# HDMI_CONN_POWER_IN.net
KiCad netlist of a schematic drawn in Altium Designer
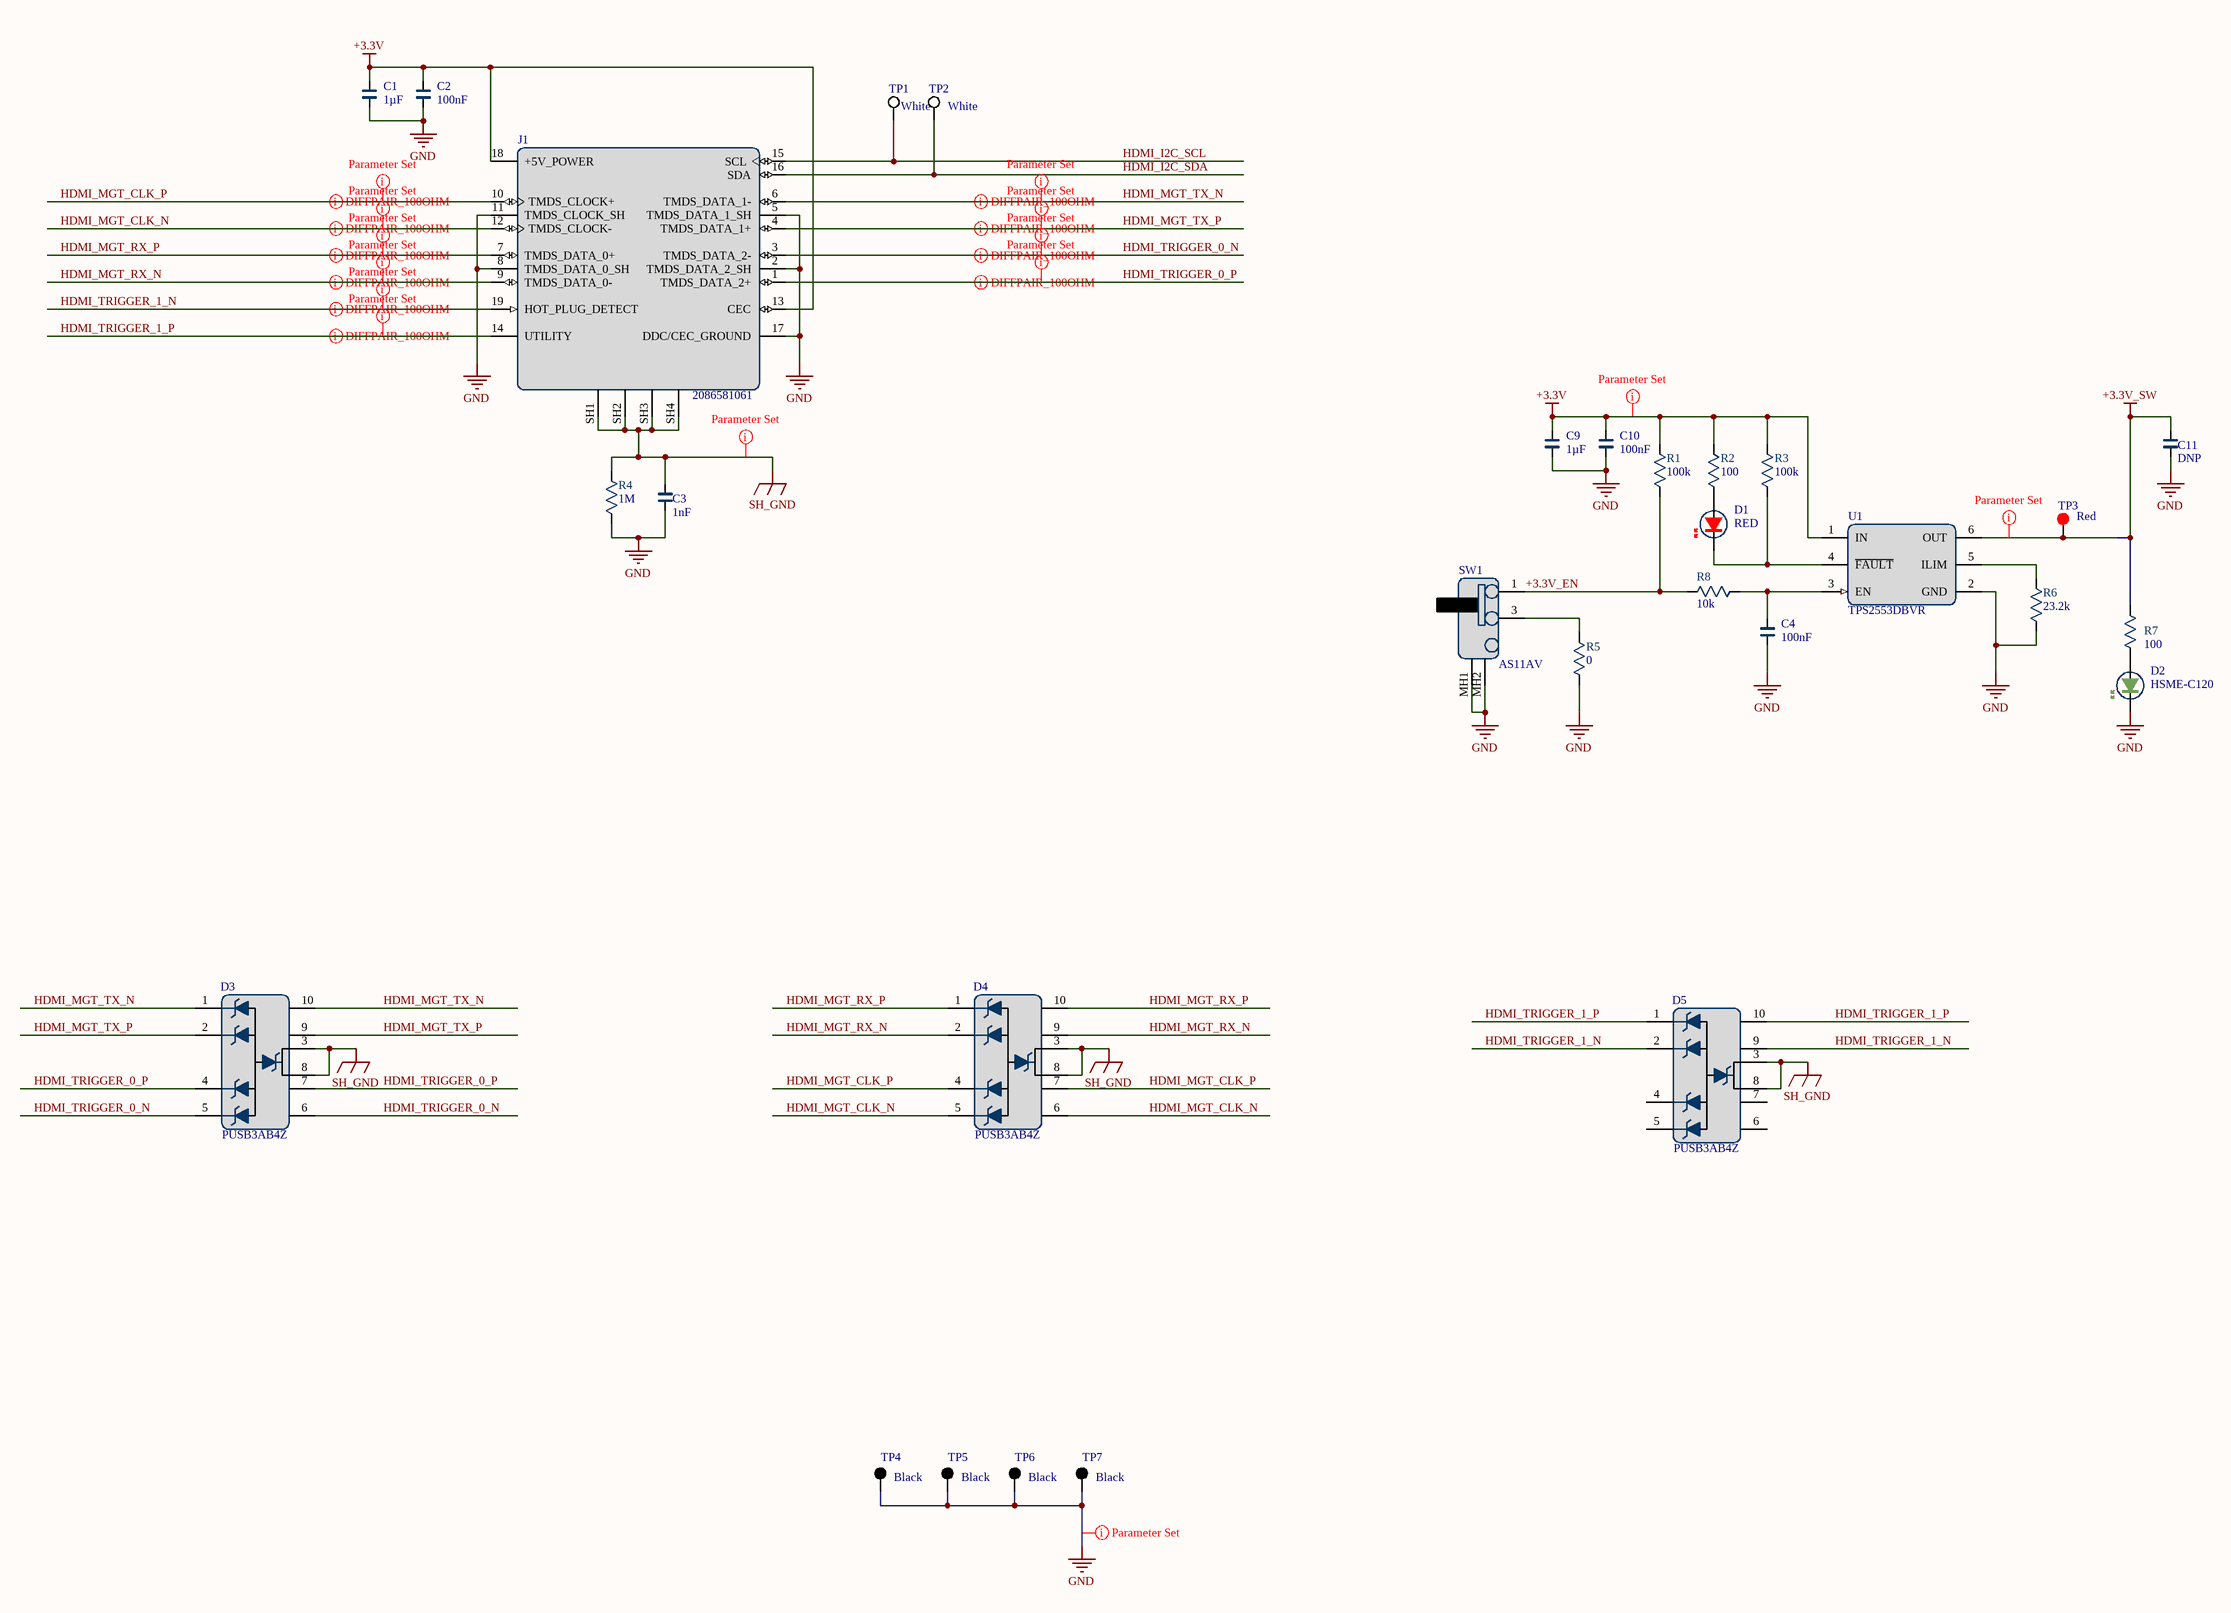
[diagram p0: HDMI_CONN_POWER_IN.SchDoc]

(export (version "E")
  (design (tool "Eeschema 10.0.6"))
  (components
    (comp (ref "C1")
      (value "1µF")
      (footprint "CAPC160X80X95L35")
      (description "CAP CER 1uF 10V 10% 0603")
      (fields (field (name "VOLTAGE") "10V") (field (name "TOLERANCE") "10%"))
      (libsource (lib "Atom Computing") (part "CAP"))
    )
    (comp (ref "C2")
      (value "100nF")
      (footprint "CAPC160X80X95L35")
      (description "CAP CER 0.1UF 25V X7R 0603")
      (fields (field (name "VOLTAGE") "25V") (field (name "TOLERANCE") "10%"))
      (libsource (lib "Atom Computing") (part "CAP"))
    )
    (comp (ref "C3")
      (value "1nF")
      (footprint "CAPC160X80X95L35")
      (description "CAP CER 1000PF 50V C0G/NPO 0603")
      (fields (field (name "TOLERANCE") "5%") (field (name "VOLTAGE") "50V"))
      (libsource (lib "Atom Computing") (part "CAP"))
    )
    (comp (ref "C4")
      (value "100nF")
      (footprint "CAPC160X80X95L35")
      (description "CAP CER 0.1UF 25V X7R 0603")
      (fields (field (name "TOLERANCE") "10%") (field (name "MFG") "Kemet"))
      (libsource (lib "Atom Computing") (part "CAP"))
    )
    (comp (ref "C9")
      (value "1µF")
      (footprint "CAPC160X80X95L35")
      (description "CAP CER 1uF 10V 10% 0603")
      (fields (field (name "VOLTAGE") "10V") (field (name "TOLERANCE") "10%"))
      (libsource (lib "Atom Computing") (part "CAP"))
    )
    (comp (ref "C10")
      (value "100nF")
      (footprint "CAPC160X80X95L35")
      (description "CAP CER 0.1UF 25V X7R 0603")
      (fields (field (name "VOLTAGE") "25V") (field (name "TOLERANCE") "10%"))
      (libsource (lib "Atom Computing") (part "CAP"))
    )
    (comp (ref "C11")
      (value "DNP")
      (footprint "CAPC200X125X145L50")
      (description "DNP, CAP 0805")
      (libsource (lib "Atom Computing") (part "CAP"))
    )
    (comp (ref "D1")
      (value "RED")
      (footprint "LEDSC80X160X55L40X70_C1A2")
      (description "LED RED CLEAR CHIP SMD 629nm, 1.9V, 0603")
      (fields (field (name "MFG") "Lite-On Inc.") (field (name "VOLTAGE") "2V"))
      (libsource (lib "Atom Computing") (part "LED_RED"))
    )
    (comp (ref "D2")
      (value "HSME-C120")
      (footprint "BROADCOM_HSMX-C120")
      (description "LED GREEN CLEAR CHIP SMD R/A")
      (fields (field (name "MFG") "AVAGO TECHNOLOGIES"))
      (libsource (lib "Atom Computing") (part "LED_GREEN"))
    )
    (comp (ref "D3")
      (value "PUSB3AB4Z")
      (footprint "NEXPERIA_PUSB3AB4Z")
      (description "TVS DIODE BIDIRECTIONAL 3.3VWM 5VC DFN2510A-10")
      (fields (field (name "MFG") "Nexperia USA Inc."))
      (libsource (lib "Atom Computing") (part "PUSB3AB4Z"))
    )
    (comp (ref "D4")
      (value "PUSB3AB4Z")
      (footprint "NEXPERIA_PUSB3AB4Z")
      (description "TVS DIODE BIDIRECTIONAL 3.3VWM 5VC DFN2510A-10")
      (fields (field (name "MFG") "Nexperia USA Inc."))
      (libsource (lib "Atom Computing") (part "PUSB3AB4Z"))
    )
    (comp (ref "D5")
      (value "PUSB3AB4Z")
      (footprint "NEXPERIA_PUSB3AB4Z")
      (description "TVS DIODE BIDIRECTIONAL 3.3VWM 5VC DFN2510A-10")
      (fields (field (name "MFG") "Nexperia USA Inc."))
      (libsource (lib "Atom Computing") (part "PUSB3AB4Z"))
    )
    (comp (ref "J1")
      (value "2086581061")
      (footprint "MOLEX_2086581061")
      (description "HDMI 2.1 Receptacle Connector 19 Position Surface Mount, Right Angle; Through Hole")
      (fields (field (name "MFG") "Molex"))
      (libsource (lib "Atom Computing") (part "HDMI Connector"))
    )
    (comp (ref "R1")
      (value "100k")
      (footprint "RESC160X85X55L30")
      (description "RES SMD 100K OHM 1% 1/10W 0603")
      (fields (field (name "MFG") "Yageo"))
      (libsource (lib "Atom Computing") (part "RES"))
    )
    (comp (ref "R2")
      (value "100")
      (footprint "RESC160X85X55L30")
      (description "RES SMD 100 OHM 1% 1/10W 0603")
      (fields (field (name "MFG") "Panasonic Electronic Components") (field (name "POWER") "100mW"))
      (libsource (lib "Atom Computing") (part "RES"))
    )
    (comp (ref "R3")
      (value "100k")
      (footprint "RESC160X85X55L30")
      (description "RES SMD 100K OHM 1% 1/10W 0603")
      (fields (field (name "MFG") "Yageo"))
      (libsource (lib "Atom Computing") (part "RES"))
    )
    (comp (ref "R4")
      (value "1M")
      (footprint "RESC320X160X76L51")
      (description "1 ±1% 0.25W, 1/4W Chip Resistor 1206 (3216 Metric) High Voltage Thick Film")
      (fields (field (name "MFG") "Vishay Dale"))
      (libsource (lib "Atom Computing") (part "RES"))
    )
    (comp (ref "R5")
      (value "0")
      (footprint "RESC160X85X55L30")
      (description "RES 0 OHM JUMPER 1/10W 0603")
      (fields (field (name "MFG") "Yageo"))
      (libsource (lib "Atom Computing") (part "RES"))
    )
    (comp (ref "R6")
      (value "23.2k")
      (footprint "RESC160X85X55L30")
      (description "RES SMD 23.2K OHM 1% 1/10W 0603")
      (fields (field (name "TOLERANCE") "1%") (field (name "POWER") "100mW"))
      (libsource (lib "Atom Computing") (part "RES"))
    )
    (comp (ref "R7")
      (value "100")
      (footprint "RESC160X85X55L30")
      (description "RES SMD 100 OHM 1% 1/10W 0603")
      (fields (field (name "MFG") "Panasonic Electronic Components") (field (name "POWER") "100mW"))
      (libsource (lib "Atom Computing") (part "RES"))
    )
    (comp (ref "R8")
      (value "10k")
      (footprint "RESC160X85X55L30")
      (description "RES SMD 10K OHM 1% 1/10W 0603")
      (fields (field (name "MFG") "Panasonic Electronic Components") (field (name "POWER") "100mW"))
      (libsource (lib "Atom Computing") (part "RES"))
    )
    (comp (ref "SW1")
      (value "AS11AV")
      (footprint "AS11AV")
      (description "SWITCH SLIDE SPST 0.4VA 28V Through Hole, Right Angle, Vertical")
      (fields (field (name "MFG") "NKK Switches") (field (name "VOLTAGE") "28V"))
      (libsource (lib "Atom Computing") (part "AS11AV"))
    )
    (comp (ref "TP1")
      (value "White")
      (footprint "Keystone_5002")
      (description "Test Point, White, 1-Pin THD, RoHS, Bulk")
      (fields (field (name "MFG") "Keystone"))
      (libsource (lib "Atom Computing") (part "TP_WHITE"))
    )
    (comp (ref "TP2")
      (value "White")
      (footprint "Keystone_5002")
      (description "Test Point, White, 1-Pin THD, RoHS, Bulk")
      (fields (field (name "MFG") "Keystone"))
      (libsource (lib "Atom Computing") (part "TP_WHITE"))
    )
    (comp (ref "TP3")
      (value "Red")
      (footprint "Keystone_5000")
      (description "Test Point, Red, 1-Pin THD, RoHS, Bulk")
      (fields (field (name "MFG") "Keystone"))
      (libsource (lib "Atom Computing") (part "TP_RED"))
    )
    (comp (ref "TP4")
      (value "Black")
      (footprint "Keystone_5001")
      (description "Test Point, Black, 1-Pin THD, RoHS, Bulk")
      (fields (field (name "MFG") "Keystone"))
      (libsource (lib "Atom Computing") (part "TP_BLACK"))
    )
    (comp (ref "TP5")
      (value "Black")
      (footprint "Keystone_5001")
      (description "Test Point, Black, 1-Pin THD, RoHS, Bulk")
      (fields (field (name "MFG") "Keystone"))
      (libsource (lib "Atom Computing") (part "TP_BLACK"))
    )
    (comp (ref "TP6")
      (value "Black")
      (footprint "Keystone_5001")
      (description "Test Point, Black, 1-Pin THD, RoHS, Bulk")
      (fields (field (name "MFG") "Keystone"))
      (libsource (lib "Atom Computing") (part "TP_BLACK"))
    )
    (comp (ref "TP7")
      (value "Black")
      (footprint "Keystone_5001")
      (description "Test Point, Black, 1-Pin THD, RoHS, Bulk")
      (fields (field (name "MFG") "Keystone"))
      (libsource (lib "Atom Computing") (part "TP_BLACK"))
    )
    (comp (ref "U1")
      (value "TPS2553DBVR")
      (footprint "SOT23-6P95_280X145L45X37")
      (description "Power Switch/Driver 1:1 N-Channel 1.5A SOT-23-6")
      (fields (field (name "MFG") "Texas Instruments"))
      (libsource (lib "Atom Computing") (part "TPS2552/3"))
    )
  )
  (nets
    (net (code "1") (name "+3.3V") (class "Default")
      (node (ref "C1") (pin "1") (pinfunction "1_1") (pintype "passive"))
      (node (ref "C10") (pin "1") (pinfunction "1_1") (pintype "passive"))
      (node (ref "C2") (pin "1") (pinfunction "1_1") (pintype "passive"))
      (node (ref "C9") (pin "1") (pinfunction "1_1") (pintype "passive"))
      (node (ref "J1") (pin "13") (pinfunction "CEC_13") (pintype "bidirectional"))
      (node (ref "J1") (pin "18") (pinfunction "+5V_POWER_18") (pintype "power_in"))
      (node (ref "R1") (pin "2") (pinfunction "2_2") (pintype "passive"))
      (node (ref "R2") (pin "2") (pinfunction "2_2") (pintype "passive"))
      (node (ref "R3") (pin "2") (pinfunction "2_2") (pintype "passive"))
      (node (ref "U1") (pin "1") (pinfunction "IN_1") (pintype "passive"))
    )
    (net (code "2") (name "+3.3V_SW") (class "Default")
      (node (ref "C11") (pin "1") (pinfunction "1_1") (pintype "passive"))
      (node (ref "R7") (pin "2") (pinfunction "2_2") (pintype "passive"))
      (node (ref "TP3") (pin "1") (pinfunction "1_1") (pintype "passive"))
      (node (ref "U1") (pin "6") (pinfunction "OUT_6") (pintype "power_in"))
    )
    (net (code "3") (name "/+3.3V_EN") (class "Default")
      (node (ref "R1") (pin "1") (pinfunction "1_1") (pintype "passive"))
      (node (ref "R8") (pin "1") (pinfunction "1_1") (pintype "passive"))
      (node (ref "SW1") (pin "1") (pinfunction "P1_1") (pintype "passive"))
    )
    (net (code "4") (name "/HDMI_I2C_SCL") (class "Default")
      (node (ref "J1") (pin "15") (pinfunction "SCL_15") (pintype "bidirectional"))
      (node (ref "TP1") (pin "1") (pinfunction "1_1") (pintype "passive"))
    )
    (net (code "5") (name "/HDMI_I2C_SDA") (class "Default")
      (node (ref "J1") (pin "16") (pinfunction "SDA_16") (pintype "bidirectional"))
      (node (ref "TP2") (pin "1") (pinfunction "1_1") (pintype "passive"))
    )
    (net (code "6") (name "/HDMI_MGT_CLK_N") (class "Default")
      (node (ref "D4") (pin "5") (pinfunction "5_5") (pintype "passive"))
      (node (ref "D4") (pin "6") (pinfunction "6_6") (pintype "passive"))
      (node (ref "J1") (pin "12") (pinfunction "TMDS_CLOCK-_12") (pintype "bidirectional"))
    )
    (net (code "7") (name "/HDMI_MGT_CLK_P") (class "Default")
      (node (ref "D4") (pin "4") (pinfunction "4_4") (pintype "passive"))
      (node (ref "D4") (pin "7") (pinfunction "7_7") (pintype "passive"))
      (node (ref "J1") (pin "10") (pinfunction "TMDS_CLOCK+_10") (pintype "bidirectional"))
    )
    (net (code "8") (name "/HDMI_MGT_RX_N") (class "Default")
      (node (ref "D4") (pin "2") (pinfunction "2_2") (pintype "passive"))
      (node (ref "D4") (pin "9") (pinfunction "9_9") (pintype "passive"))
      (node (ref "J1") (pin "9") (pinfunction "TMDS_DATA_0-_9") (pintype "bidirectional"))
    )
    (net (code "9") (name "/HDMI_MGT_RX_P") (class "Default")
      (node (ref "D4") (pin "1") (pinfunction "1_1") (pintype "passive"))
      (node (ref "D4") (pin "10") (pinfunction "10_10") (pintype "passive"))
      (node (ref "J1") (pin "7") (pinfunction "TMDS_DATA_0+_7") (pintype "bidirectional"))
    )
    (net (code "10") (name "/HDMI_MGT_TX_N") (class "Default")
      (node (ref "D3") (pin "1") (pinfunction "1_1") (pintype "passive"))
      (node (ref "D3") (pin "10") (pinfunction "10_10") (pintype "passive"))
      (node (ref "J1") (pin "6") (pinfunction "TMDS_DATA_1-_6") (pintype "bidirectional"))
    )
    (net (code "11") (name "/HDMI_MGT_TX_P") (class "Default")
      (node (ref "D3") (pin "2") (pinfunction "2_2") (pintype "passive"))
      (node (ref "D3") (pin "9") (pinfunction "9_9") (pintype "passive"))
      (node (ref "J1") (pin "4") (pinfunction "TMDS_DATA_1+_4") (pintype "bidirectional"))
    )
    (net (code "12") (name "/HDMI_TRIGGER_0_N") (class "Default")
      (node (ref "D3") (pin "5") (pinfunction "5_5") (pintype "passive"))
      (node (ref "D3") (pin "6") (pinfunction "6_6") (pintype "passive"))
      (node (ref "J1") (pin "3") (pinfunction "TMDS_DATA_2-_3") (pintype "bidirectional"))
    )
    (net (code "13") (name "/HDMI_TRIGGER_0_P") (class "Default")
      (node (ref "D3") (pin "4") (pinfunction "4_4") (pintype "passive"))
      (node (ref "D3") (pin "7") (pinfunction "7_7") (pintype "passive"))
      (node (ref "J1") (pin "1") (pinfunction "TMDS_DATA_2+_1") (pintype "bidirectional"))
    )
    (net (code "14") (name "/HDMI_TRIGGER_1_N") (class "Default")
      (node (ref "D5") (pin "2") (pinfunction "2_2") (pintype "passive"))
      (node (ref "D5") (pin "9") (pinfunction "9_9") (pintype "passive"))
      (node (ref "J1") (pin "19") (pinfunction "HOT_PLUG_DETECT_19") (pintype "input"))
    )
    (net (code "15") (name "/HDMI_TRIGGER_1_P") (class "Default")
      (node (ref "D5") (pin "1") (pinfunction "1_1") (pintype "passive"))
      (node (ref "D5") (pin "10") (pinfunction "10_10") (pintype "passive"))
      (node (ref "J1") (pin "14") (pinfunction "UTILITY_14") (pintype "passive"))
    )
    (net (code "16") (name "GND") (class "Default")
      (node (ref "C1") (pin "2") (pinfunction "2_2") (pintype "passive"))
      (node (ref "C10") (pin "2") (pinfunction "2_2") (pintype "passive"))
      (node (ref "C11") (pin "2") (pinfunction "2_2") (pintype "passive"))
      (node (ref "C2") (pin "2") (pinfunction "2_2") (pintype "passive"))
      (node (ref "C3") (pin "2") (pinfunction "2_2") (pintype "passive"))
      (node (ref "C4") (pin "2") (pinfunction "2_2") (pintype "passive"))
      (node (ref "C9") (pin "2") (pinfunction "2_2") (pintype "passive"))
      (node (ref "D2") (pin "1") (pinfunction "1_1") (pintype "passive"))
      (node (ref "J1") (pin "11") (pinfunction "TMDS_CLOCK_SH_11") (pintype "passive"))
      (node (ref "J1") (pin "17") (pinfunction "DDC/CEC_GROUND_17") (pintype "power_in"))
      (node (ref "J1") (pin "2") (pinfunction "TMDS_DATA_2_SH_2") (pintype "passive"))
      (node (ref "J1") (pin "5") (pinfunction "TMDS_DATA_1_SH_5") (pintype "passive"))
      (node (ref "J1") (pin "8") (pinfunction "TMDS_DATA_0_SH_8") (pintype "passive"))
      (node (ref "R4") (pin "1") (pinfunction "1_1") (pintype "passive"))
      (node (ref "R5") (pin "2") (pinfunction "2_2") (pintype "passive"))
      (node (ref "R6") (pin "1") (pinfunction "1_1") (pintype "passive"))
      (node (ref "SW1") (pin "MH1") (pinfunction "P4_MH1") (pintype "power_in"))
      (node (ref "SW1") (pin "MH2") (pinfunction "P5_MH2") (pintype "power_in"))
      (node (ref "TP4") (pin "1") (pinfunction "1_1") (pintype "passive"))
      (node (ref "TP5") (pin "1") (pinfunction "1_1") (pintype "passive"))
      (node (ref "TP6") (pin "1") (pinfunction "1_1") (pintype "passive"))
      (node (ref "TP7") (pin "1") (pinfunction "1_1") (pintype "passive"))
      (node (ref "U1") (pin "2") (pinfunction "GND_2") (pintype "passive"))
    )
    (net (code "17") (name "Net-(D1-Pad2)") (class "Default")
      (node (ref "D1") (pin "2") (pinfunction "2_2") (pintype "passive"))
      (node (ref "R2") (pin "1") (pinfunction "1_1") (pintype "passive"))
    )
    (net (code "18") (name "Net-(D2-Pad2)") (class "Default")
      (node (ref "D2") (pin "2") (pinfunction "2_2") (pintype "passive"))
      (node (ref "R7") (pin "1") (pinfunction "1_1") (pintype "passive"))
    )
    (net (code "19") (name "Net-(SW1-P3)") (class "Default")
      (node (ref "R5") (pin "1") (pinfunction "1_1") (pintype "passive"))
      (node (ref "SW1") (pin "3") (pinfunction "P3_3") (pintype "passive"))
    )
    (net (code "20") (name "Net-(U1-EN)") (class "Default")
      (node (ref "C4") (pin "1") (pinfunction "1_1") (pintype "passive"))
      (node (ref "R8") (pin "2") (pinfunction "2_2") (pintype "passive"))
      (node (ref "U1") (pin "3") (pinfunction "EN_3") (pintype "input"))
    )
    (net (code "21") (name "Net-(U1-ILIM)") (class "Default")
      (node (ref "R6") (pin "2") (pinfunction "2_2") (pintype "passive"))
      (node (ref "U1") (pin "5") (pinfunction "ILIM_5") (pintype "passive"))
    )
    (net (code "22") (name "Net-(U1-~{FAULT})") (class "Default")
      (node (ref "D1") (pin "1") (pinfunction "1_1") (pintype "passive"))
      (node (ref "R3") (pin "1") (pinfunction "1_1") (pintype "passive"))
      (node (ref "U1") (pin "4") (pinfunction "~{FAULT}_4") (pintype "power_in"))
    )
    (net (code "23") (name "SH_GND") (class "Default")
      (node (ref "C3") (pin "1") (pinfunction "1_1") (pintype "passive"))
      (node (ref "D3") (pin "3") (pinfunction "3_3") (pintype "passive"))
      (node (ref "D3") (pin "8") (pinfunction "8_8") (pintype "passive"))
      (node (ref "D4") (pin "3") (pinfunction "3_3") (pintype "passive"))
      (node (ref "D4") (pin "8") (pinfunction "8_8") (pintype "passive"))
      (node (ref "D5") (pin "3") (pinfunction "3_3") (pintype "passive"))
      (node (ref "D5") (pin "8") (pinfunction "8_8") (pintype "passive"))
      (node (ref "J1") (pin "SH1") (pinfunction "SHLD1_SH1") (pintype "passive"))
      (node (ref "J1") (pin "SH2") (pinfunction "SHLD2_SH2") (pintype "passive"))
      (node (ref "J1") (pin "SH3") (pinfunction "SHLD3_SH3") (pintype "passive"))
      (node (ref "J1") (pin "SH4") (pinfunction "SHLD4_SH4") (pintype "passive"))
      (node (ref "R4") (pin "2") (pinfunction "2_2") (pintype "passive"))
    )
    (net (code "24") (name "unconnected-(D5-Pad4)") (class "Default")
      (node (ref "D5") (pin "4") (pinfunction "4_4") (pintype "passive"))
    )
    (net (code "25") (name "unconnected-(D5-Pad5)") (class "Default")
      (node (ref "D5") (pin "5") (pinfunction "5_5") (pintype "passive"))
    )
    (net (code "26") (name "unconnected-(D5-Pad6)") (class "Default")
      (node (ref "D5") (pin "6") (pinfunction "6_6") (pintype "passive"))
    )
    (net (code "27") (name "unconnected-(D5-Pad7)") (class "Default")
      (node (ref "D5") (pin "7") (pinfunction "7_7") (pintype "passive"))
    )
  )
)
